# Hoja_Fuente.net
KiCad netlist of a schematic drawn in Altium Designer
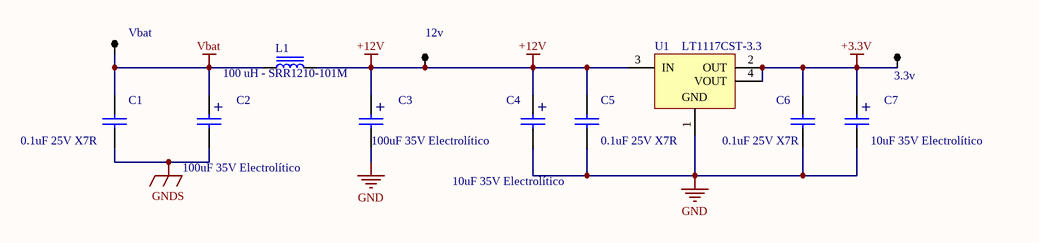
[diagram p0: Hoja_Fuente.SchDoc]

(export (version "E")
  (design (tool "Eeschema 10.0.6"))
  (components
    (comp (ref "3.3v") (value "3.3v") (footprint "TPTH") (libsource (lib "Libreria_Casera") (part "TP")))
    (comp (ref "12v") (value "12v") (footprint "TPTH") (libsource (lib "Libreria_Casera") (part "TP")))
    (comp (ref "C1")
      (value "0.1uF 25V X7R")
      (footprint "0805")
      (libsource (lib "Libreria_Casera") (part "CAP"))
    )
    (comp (ref "C2")
      (value "100uF 35V Electrolítico")
      (footprint "CAPSMD8x8.3")
      (libsource (lib "LIBEBAL") (part "CAPPOL"))
    )
    (comp (ref "C3")
      (value "100uF 35V Electrolítico")
      (footprint "CAPSMD8x8.3")
      (libsource (lib "LIBEBAL") (part "CAPPOL"))
    )
    (comp (ref "C4")
      (value "10uF 35V Electrolítico")
      (footprint "CAPSMD4.3x4.3")
      (libsource (lib "LIBEBAL") (part "CAPPOL"))
    )
    (comp (ref "C5")
      (value "0.1uF 25V X7R")
      (footprint "0805")
      (libsource (lib "Libreria_Casera") (part "CAP"))
    )
    (comp (ref "C6")
      (value "0.1uF 25V X7R")
      (footprint "0805")
      (libsource (lib "Libreria_Casera") (part "CAP"))
    )
    (comp (ref "C7")
      (value "10uF 35V Electrolítico")
      (footprint "CAPSMD4.3x4.3")
      (libsource (lib "LIBEBAL") (part "CAPPOL"))
    )
    (comp (ref "L1")
      (value "100 uH - SRR1210-101M")
      (footprint "SRR1210")
      (description "SRR1210-101M - 100 µH Blindado Drum Core, Wirewound Inductivo 2.5 A 135mOhm máx. No estándar")
      (libsource (lib "Libreria_Casera") (part "INDUCTOR"))
    )
    (comp (ref "U1")
      (value "LT1117CST-3.3")
      (footprint "SOT223")
      (description "IC REG LINEAR 3.3V 800MA SOT223")
      (fields (field (name "MANUFACTURER") "Linear Technology"))
      (libsource (lib "Linear Technology Power Management LDO Linear Regulators") (part "LT1117CST-3.3"))
    )
    (comp (ref "Vbat") (value "Vbat") (footprint "TPTH") (libsource (lib "Libreria_Casera") (part "TP")))
  )
  (nets
    (net (code "1") (name "+3.3V") (class "Default")
      (node (ref "3.3v") (pin "1") (pinfunction "1_1") (pintype "passive"))
      (node (ref "C6") (pin "1") (pinfunction "1_1") (pintype "passive"))
      (node (ref "C7") (pin "1") (pinfunction "1_1") (pintype "passive"))
      (node (ref "U1") (pin "2") (pinfunction "OUT_2") (pintype "power_in"))
      (node (ref "U1") (pin "4") (pinfunction "VOUT_4") (pintype "power_in"))
    )
    (net (code "2") (name "+12V") (class "Default")
      (node (ref "12v") (pin "1") (pinfunction "1_1") (pintype "passive"))
      (node (ref "C3") (pin "1") (pinfunction "1_1") (pintype "passive"))
      (node (ref "C4") (pin "1") (pinfunction "1_1") (pintype "passive"))
      (node (ref "C5") (pin "1") (pinfunction "1_1") (pintype "passive"))
      (node (ref "L1") (pin "2") (pinfunction "2_2") (pintype "passive"))
      (node (ref "U1") (pin "3") (pinfunction "IN_3") (pintype "power_in"))
    )
    (net (code "3") (name "GND") (class "Default")
      (node (ref "C3") (pin "2") (pinfunction "2_2") (pintype "passive"))
      (node (ref "C4") (pin "2") (pinfunction "2_2") (pintype "passive"))
      (node (ref "C5") (pin "2") (pinfunction "2_2") (pintype "passive"))
      (node (ref "C6") (pin "2") (pinfunction "2_2") (pintype "passive"))
      (node (ref "C7") (pin "2") (pinfunction "2_2") (pintype "passive"))
      (node (ref "U1") (pin "1") (pinfunction "GND_1") (pintype "power_in"))
    )
    (net (code "4") (name "GNDS") (class "Default")
      (node (ref "C1") (pin "2") (pinfunction "2_2") (pintype "passive"))
      (node (ref "C2") (pin "2") (pinfunction "2_2") (pintype "passive"))
    )
    (net (code "5") (name "Vbat") (class "Default")
      (node (ref "C1") (pin "1") (pinfunction "1_1") (pintype "passive"))
      (node (ref "C2") (pin "1") (pinfunction "1_1") (pintype "passive"))
      (node (ref "L1") (pin "1") (pinfunction "1_1") (pintype "passive"))
      (node (ref "Vbat") (pin "1") (pinfunction "1_1") (pintype "passive"))
    )
  )
)
